# Sheet1.net
KiCad netlist of a schematic drawn in Altium Designer
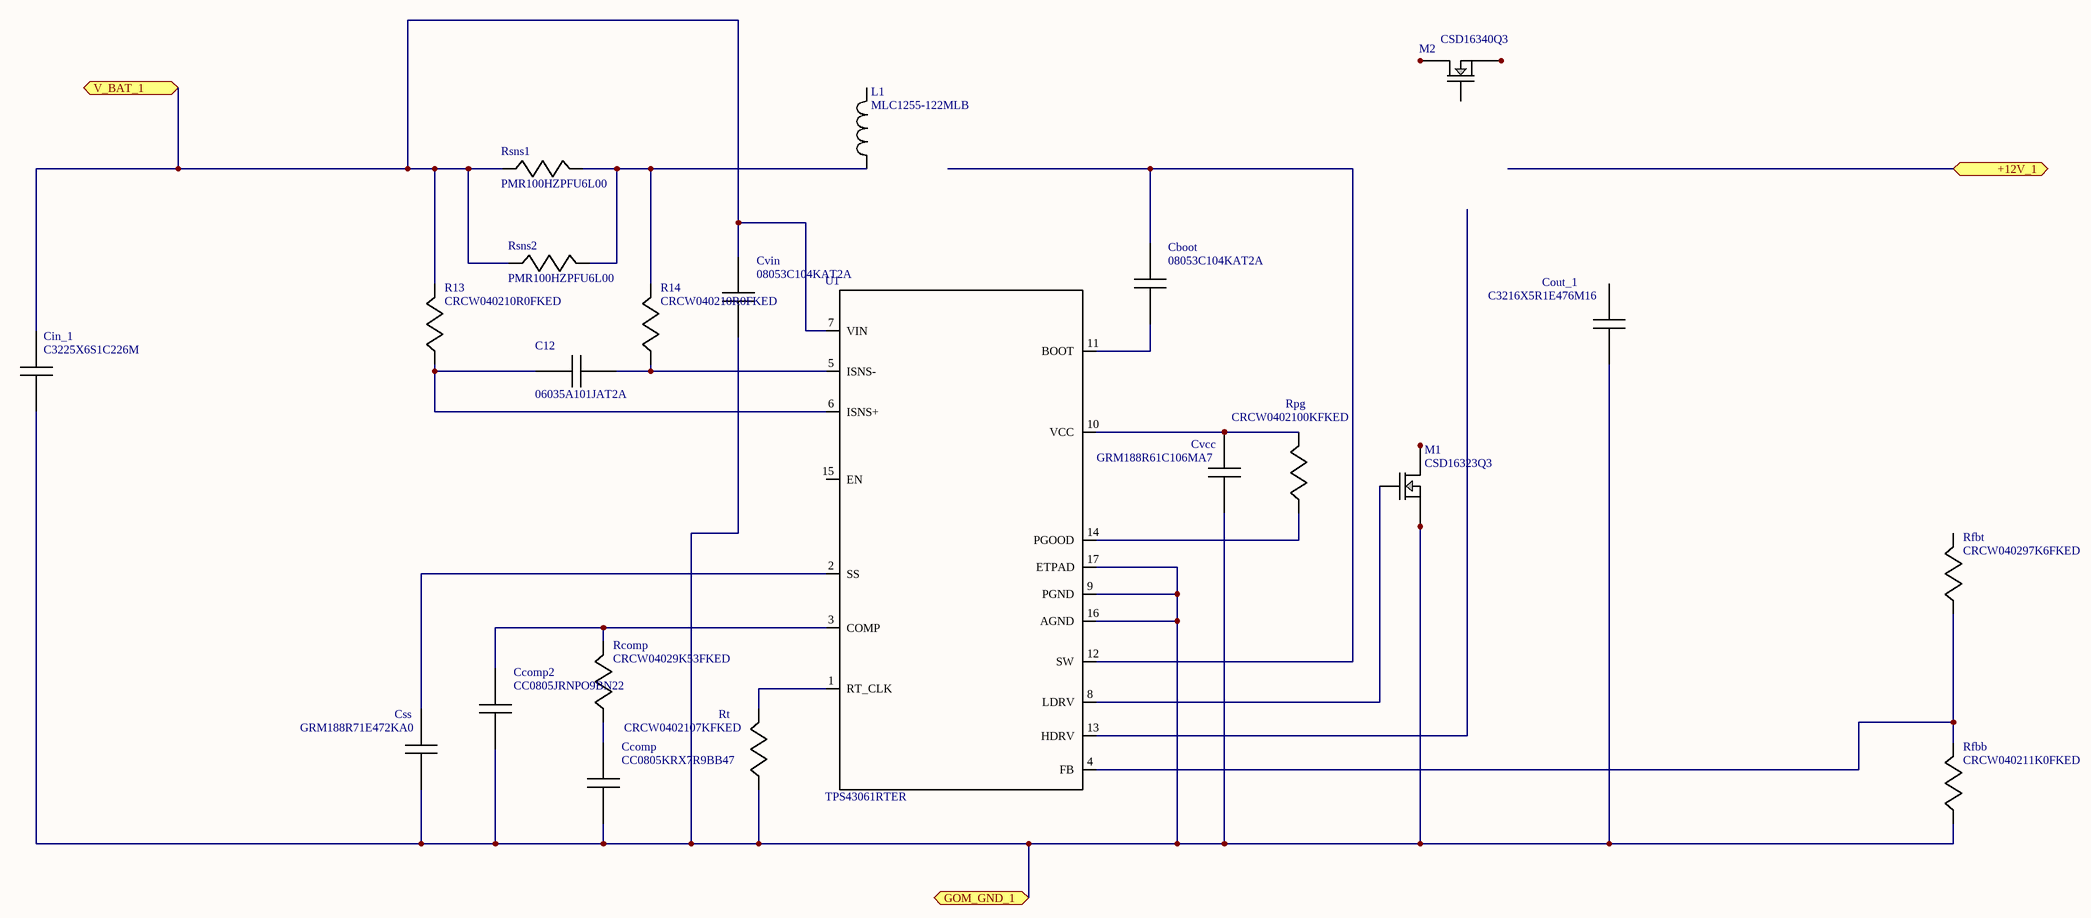
[diagram p0: Sheet1.SchDoc]

(export (version "E")
  (design (tool "Eeschema 10.0.6"))
  (components
    (comp (ref "C12")
      (value "06035A101JAT2A")
      (footprint "0603")
      (description "Imported")
      (libsource (lib "2016-03-26_18-23-46") (part "06035A101JAT2A"))
    )
    (comp (ref "Cboot")
      (value "08053C104KAT2A")
      (footprint "0805")
      (description "Imported")
      (libsource (lib "2016-03-26_18-23-46") (part "08053C104KAT2A"))
    )
    (comp (ref "Ccomp")
      (value "CC0805KRX7R9BB47")
      (footprint "0805")
      (description "Imported")
      (fields (field (name "MANUFACTURER_PART_NUMBER") "CC0805KRX7R9BB472"))
      (libsource (lib "2016-03-26_18-23-46") (part "CC0805KRX7R9BB47"))
    )
    (comp (ref "Ccomp2")
      (value "CC0805JRNPO9BN22")
      (footprint "0805")
      (description "Imported")
      (fields (field (name "MANUFACTURER_PART_NUMBER") "CC0805JRNPO9BN221"))
      (libsource (lib "2016-03-26_18-23-46") (part "CC0805JRNPO9BN22"))
    )
    (comp (ref "Cin_1")
      (value "C3225X6S1C226M")
      (footprint "1210")
      (description "Imported")
      (libsource (lib "2016-03-26_18-23-46") (part "C3225X6S1C226M"))
    )
    (comp (ref "Cout_1")
      (value "C3216X5R1E476M16")
      (footprint "1206_190")
      (description "Imported")
      (fields (field (name "MANUFACTURER_PART_NUMBER") "C3216X5R1E476M160AC"))
      (libsource (lib "2016-03-26_18-23-46") (part "C3216X5R1E476M16"))
    )
    (comp (ref "Css")
      (value "GRM188R71E472KA0")
      (footprint "0603")
      (description "Imported")
      (fields (field (name "MANUFACTURER_PART_NUMBER") "GRM188R71E472KA01D"))
      (libsource (lib "2016-03-26_18-23-46") (part "GRM188R71E472KA0"))
    )
    (comp (ref "Cvcc")
      (value "GRM188R61C106MA7")
      (footprint "0603")
      (description "Imported")
      (fields (field (name "MANUFACTURER_PART_NUMBER") "GRM188R61C106MA73D"))
      (libsource (lib "2016-03-26_18-23-46") (part "GRM188R61C106MA7"))
    )
    (comp (ref "Cvin")
      (value "08053C104KAT2A")
      (footprint "0805")
      (description "Imported")
      (libsource (lib "2016-03-26_18-23-46") (part "08053C104KAT2A"))
    )
    (comp (ref "L1")
      (value "MLC1255-122MLB")
      (footprint "MLC1255")
      (description "Imported")
      (libsource (lib "2016-03-26_18-23-46") (part "MLC1255-122MLB"))
    )
    (comp (ref "M1")
      (value "CSD16323Q3")
      (footprint "TRANS_NexFET_Q3")
      (description "Imported")
      (libsource (lib "2016-03-26_18-23-46") (part "CSD16323Q3"))
    )
    (comp (ref "M2")
      (value "CSD16340Q3")
      (footprint "TRANS_NexFET_Q3")
      (description "Imported")
      (libsource (lib "2016-03-26_18-23-46") (part "CSD16340Q3"))
    )
    (comp (ref "R13")
      (value "CRCW040210R0FKED")
      (footprint "0402")
      (description "Imported")
      (libsource (lib "2016-03-26_18-23-46") (part "CRCW040210R0FKED"))
    )
    (comp (ref "R14")
      (value "CRCW040210R0FKED")
      (footprint "0402")
      (description "Imported")
      (libsource (lib "2016-03-26_18-23-46") (part "CRCW040210R0FKED"))
    )
    (comp (ref "Rcomp")
      (value "CRCW04029K53FKED")
      (footprint "0402")
      (description "Imported")
      (libsource (lib "2016-03-26_18-23-46") (part "CRCW04029K53FKED"))
    )
    (comp (ref "Rfbb")
      (value "CRCW040211K0FKED")
      (footprint "0402")
      (description "Imported")
      (libsource (lib "2016-03-26_18-23-46") (part "CRCW040211K0FKED"))
    )
    (comp (ref "Rfbt")
      (value "CRCW040297K6FKED")
      (footprint "0402")
      (description "Imported")
      (libsource (lib "2016-03-26_18-23-46") (part "CRCW040297K6FKED"))
    )
    (comp (ref "Rpg")
      (value "CRCW0402100KFKED")
      (footprint "0402")
      (description "Imported")
      (libsource (lib "2016-03-26_18-23-46") (part "CRCW0402100KFKED"))
    )
    (comp (ref "Rsns1")
      (value "PMR100HZPFU6L00")
      (footprint "2512")
      (description "Imported")
      (libsource (lib "2016-03-26_18-23-46") (part "PMR100HZPFU6L00"))
    )
    (comp (ref "Rsns2")
      (value "PMR100HZPFU6L00")
      (footprint "2512")
      (description "Imported")
      (libsource (lib "2016-03-26_18-23-46") (part "PMR100HZPFU6L00"))
    )
    (comp (ref "Rt")
      (value "CRCW0402107KFKED")
      (footprint "0402")
      (description "Imported")
      (libsource (lib "2016-03-26_18-23-46") (part "CRCW0402107KFKED"))
    )
    (comp (ref "U1")
      (value "TPS43061RTER")
      (footprint "S-PVQFN-N16")
      (description "Imported")
      (libsource (lib "2016-03-26_18-23-46") (part "TPS43061RTER"))
    )
  )
  (nets
    (net (code "2") (name "/GOM_GND_1") (class "Default")
      (node (ref "Ccomp") (pin "2") (pinfunction "2_2") (pintype "passive"))
      (node (ref "Ccomp2") (pin "2") (pinfunction "2_2") (pintype "passive"))
      (node (ref "Cin_1") (pin "2") (pinfunction "2_2") (pintype "passive"))
      (node (ref "Cout_1") (pin "2") (pinfunction "2_2") (pintype "passive"))
      (node (ref "Css") (pin "1") (pinfunction "1_1") (pintype "passive"))
      (node (ref "Cvcc") (pin "2") (pinfunction "2_2") (pintype "passive"))
      (node (ref "Cvin") (pin "2") (pinfunction "2_2") (pintype "passive"))
      (node (ref "M1") (pin "1") (pinfunction "Source_1") (pintype "passive"))
      (node (ref "M1") (pin "2") (pinfunction "Source_2") (pintype "passive"))
      (node (ref "M1") (pin "3") (pinfunction "Source_3") (pintype "passive"))
      (node (ref "Rfbb") (pin "2") (pinfunction "2_2") (pintype "passive"))
      (node (ref "Rt") (pin "2") (pinfunction "2_2") (pintype "passive"))
      (node (ref "U1") (pin "16") (pinfunction "AGND_16") (pintype "passive"))
      (node (ref "U1") (pin "17") (pinfunction "ETPAD_17") (pintype "passive"))
      (node (ref "U1") (pin "9") (pinfunction "PGND_9") (pintype "passive"))
    )
    (net (code "3") (name "/V_BAT_1") (class "Default")
      (node (ref "Cin_1") (pin "1") (pinfunction "1_1") (pintype "passive"))
      (node (ref "Cvin") (pin "1") (pinfunction "1_1") (pintype "passive"))
      (node (ref "R13") (pin "1") (pinfunction "1_1") (pintype "passive"))
      (node (ref "Rsns1") (pin "2") (pinfunction "2_2") (pintype "passive"))
      (node (ref "Rsns2") (pin "2") (pinfunction "2_2") (pintype "passive"))
      (node (ref "U1") (pin "7") (pinfunction "VIN_7") (pintype "passive"))
    )
    (net (code "4") (name "Net-(Ccomp-Pad1)") (class "Default")
      (node (ref "Ccomp") (pin "1") (pinfunction "1_1") (pintype "passive"))
      (node (ref "Rcomp") (pin "2") (pinfunction "2_2") (pintype "passive"))
    )
    (net (code "5") (name "Net-(L1-Pad1)") (class "Default")
      (node (ref "L1") (pin "1") (pinfunction "1_1") (pintype "passive"))
      (node (ref "R14") (pin "1") (pinfunction "1_1") (pintype "passive"))
      (node (ref "Rsns1") (pin "1") (pinfunction "1_1") (pintype "passive"))
      (node (ref "Rsns2") (pin "1") (pinfunction "1_1") (pintype "passive"))
    )
    (net (code "6") (name "Net-(M1-Drain-Pad5)") (class "Default")
      (node (ref "M1") (pin "5") (pinfunction "Drain_5") (pintype "passive"))
      (node (ref "M1") (pin "6") (pinfunction "Drain_6") (pintype "passive"))
      (node (ref "M1") (pin "7") (pinfunction "Drain_7") (pintype "passive"))
      (node (ref "M1") (pin "8") (pinfunction "Drain_8") (pintype "passive"))
      (node (ref "M1") (pin "9") (pinfunction "Drain_9") (pintype "passive"))
    )
    (net (code "7") (name "Net-(M1-Gate)") (class "Default")
      (node (ref "M1") (pin "4") (pinfunction "Gate_4") (pintype "passive"))
      (node (ref "U1") (pin "8") (pinfunction "LDRV_8") (pintype "passive"))
    )
    (net (code "8") (name "Net-(M2-Drain-Pad5)") (class "Default")
      (node (ref "M2") (pin "5") (pinfunction "Drain_5") (pintype "passive"))
      (node (ref "M2") (pin "6") (pinfunction "Drain_6") (pintype "passive"))
      (node (ref "M2") (pin "7") (pinfunction "Drain_7") (pintype "passive"))
      (node (ref "M2") (pin "8") (pinfunction "Drain_8") (pintype "passive"))
      (node (ref "M2") (pin "9") (pinfunction "Drain_9") (pintype "passive"))
    )
    (net (code "9") (name "Net-(M2-Source-Pad1)") (class "Default")
      (node (ref "M2") (pin "1") (pinfunction "Source_1") (pintype "passive"))
      (node (ref "M2") (pin "2") (pinfunction "Source_2") (pintype "passive"))
      (node (ref "M2") (pin "3") (pinfunction "Source_3") (pintype "passive"))
    )
    (net (code "10") (name "Net-(U1-BOOT)") (class "Default")
      (node (ref "Cboot") (pin "2") (pinfunction "2_2") (pintype "passive"))
      (node (ref "U1") (pin "11") (pinfunction "BOOT_11") (pintype "passive"))
    )
    (net (code "11") (name "Net-(U1-COMP)") (class "Default")
      (node (ref "Ccomp2") (pin "1") (pinfunction "1_1") (pintype "passive"))
      (node (ref "Rcomp") (pin "1") (pinfunction "1_1") (pintype "passive"))
      (node (ref "U1") (pin "3") (pinfunction "COMP_3") (pintype "passive"))
    )
    (net (code "12") (name "Net-(U1-FB)") (class "Default")
      (node (ref "Rfbb") (pin "1") (pinfunction "1_1") (pintype "passive"))
      (node (ref "Rfbt") (pin "2") (pinfunction "2_2") (pintype "passive"))
      (node (ref "U1") (pin "4") (pinfunction "FB_4") (pintype "passive"))
    )
    (net (code "13") (name "Net-(U1-ISNS+)") (class "Default")
      (node (ref "C12") (pin "2") (pinfunction "2_2") (pintype "passive"))
      (node (ref "R13") (pin "2") (pinfunction "2_2") (pintype "passive"))
      (node (ref "U1") (pin "6") (pinfunction "ISNS+_6") (pintype "passive"))
    )
    (net (code "14") (name "Net-(U1-ISNS-)") (class "Default")
      (node (ref "C12") (pin "1") (pinfunction "1_1") (pintype "passive"))
      (node (ref "R14") (pin "2") (pinfunction "2_2") (pintype "passive"))
      (node (ref "U1") (pin "5") (pinfunction "ISNS-_5") (pintype "passive"))
    )
    (net (code "15") (name "Net-(U1-PGOOD)") (class "Default")
      (node (ref "Rpg") (pin "2") (pinfunction "2_2") (pintype "passive"))
      (node (ref "U1") (pin "14") (pinfunction "PGOOD_14") (pintype "passive"))
    )
    (net (code "16") (name "Net-(U1-RT_CLK)") (class "Default")
      (node (ref "Rt") (pin "1") (pinfunction "1_1") (pintype "passive"))
      (node (ref "U1") (pin "1") (pinfunction "RT_CLK_1") (pintype "passive"))
    )
    (net (code "17") (name "Net-(U1-SS)") (class "Default")
      (node (ref "Css") (pin "2") (pinfunction "2_2") (pintype "passive"))
      (node (ref "U1") (pin "2") (pinfunction "SS_2") (pintype "passive"))
    )
    (net (code "18") (name "Net-(U1-SW)") (class "Default")
      (node (ref "Cboot") (pin "1") (pinfunction "1_1") (pintype "passive"))
      (node (ref "U1") (pin "12") (pinfunction "SW_12") (pintype "passive"))
    )
    (net (code "19") (name "Net-(U1-VCC)") (class "Default")
      (node (ref "Cvcc") (pin "1") (pinfunction "1_1") (pintype "passive"))
      (node (ref "Rpg") (pin "1") (pinfunction "1_1") (pintype "passive"))
      (node (ref "U1") (pin "10") (pinfunction "VCC_10") (pintype "passive"))
    )
    (net (code "20") (name "unconnected-(Cout_1-Pad1)") (class "Default")
      (node (ref "Cout_1") (pin "1") (pinfunction "1_1") (pintype "passive"))
    )
    (net (code "21") (name "unconnected-(L1-Pad2)") (class "Default")
      (node (ref "L1") (pin "2") (pinfunction "2_2") (pintype "passive"))
    )
    (net (code "22") (name "unconnected-(M2-Gate-Pad4)") (class "Default")
      (node (ref "M2") (pin "4") (pinfunction "Gate_4") (pintype "passive"))
    )
    (net (code "23") (name "unconnected-(Rfbt-Pad1)") (class "Default")
      (node (ref "Rfbt") (pin "1") (pinfunction "1_1") (pintype "passive"))
    )
    (net (code "24") (name "unconnected-(U1-EN-Pad15)") (class "Default")
      (node (ref "U1") (pin "15") (pinfunction "EN_15") (pintype "passive"))
    )
    (net (code "25") (name "unconnected-(U1-HDRV-Pad13)") (class "Default")
      (node (ref "U1") (pin "13") (pinfunction "HDRV_13") (pintype "passive"))
    )
  )
)
